# 1_Power.net
KiCad netlist of a schematic drawn in Altium Designer
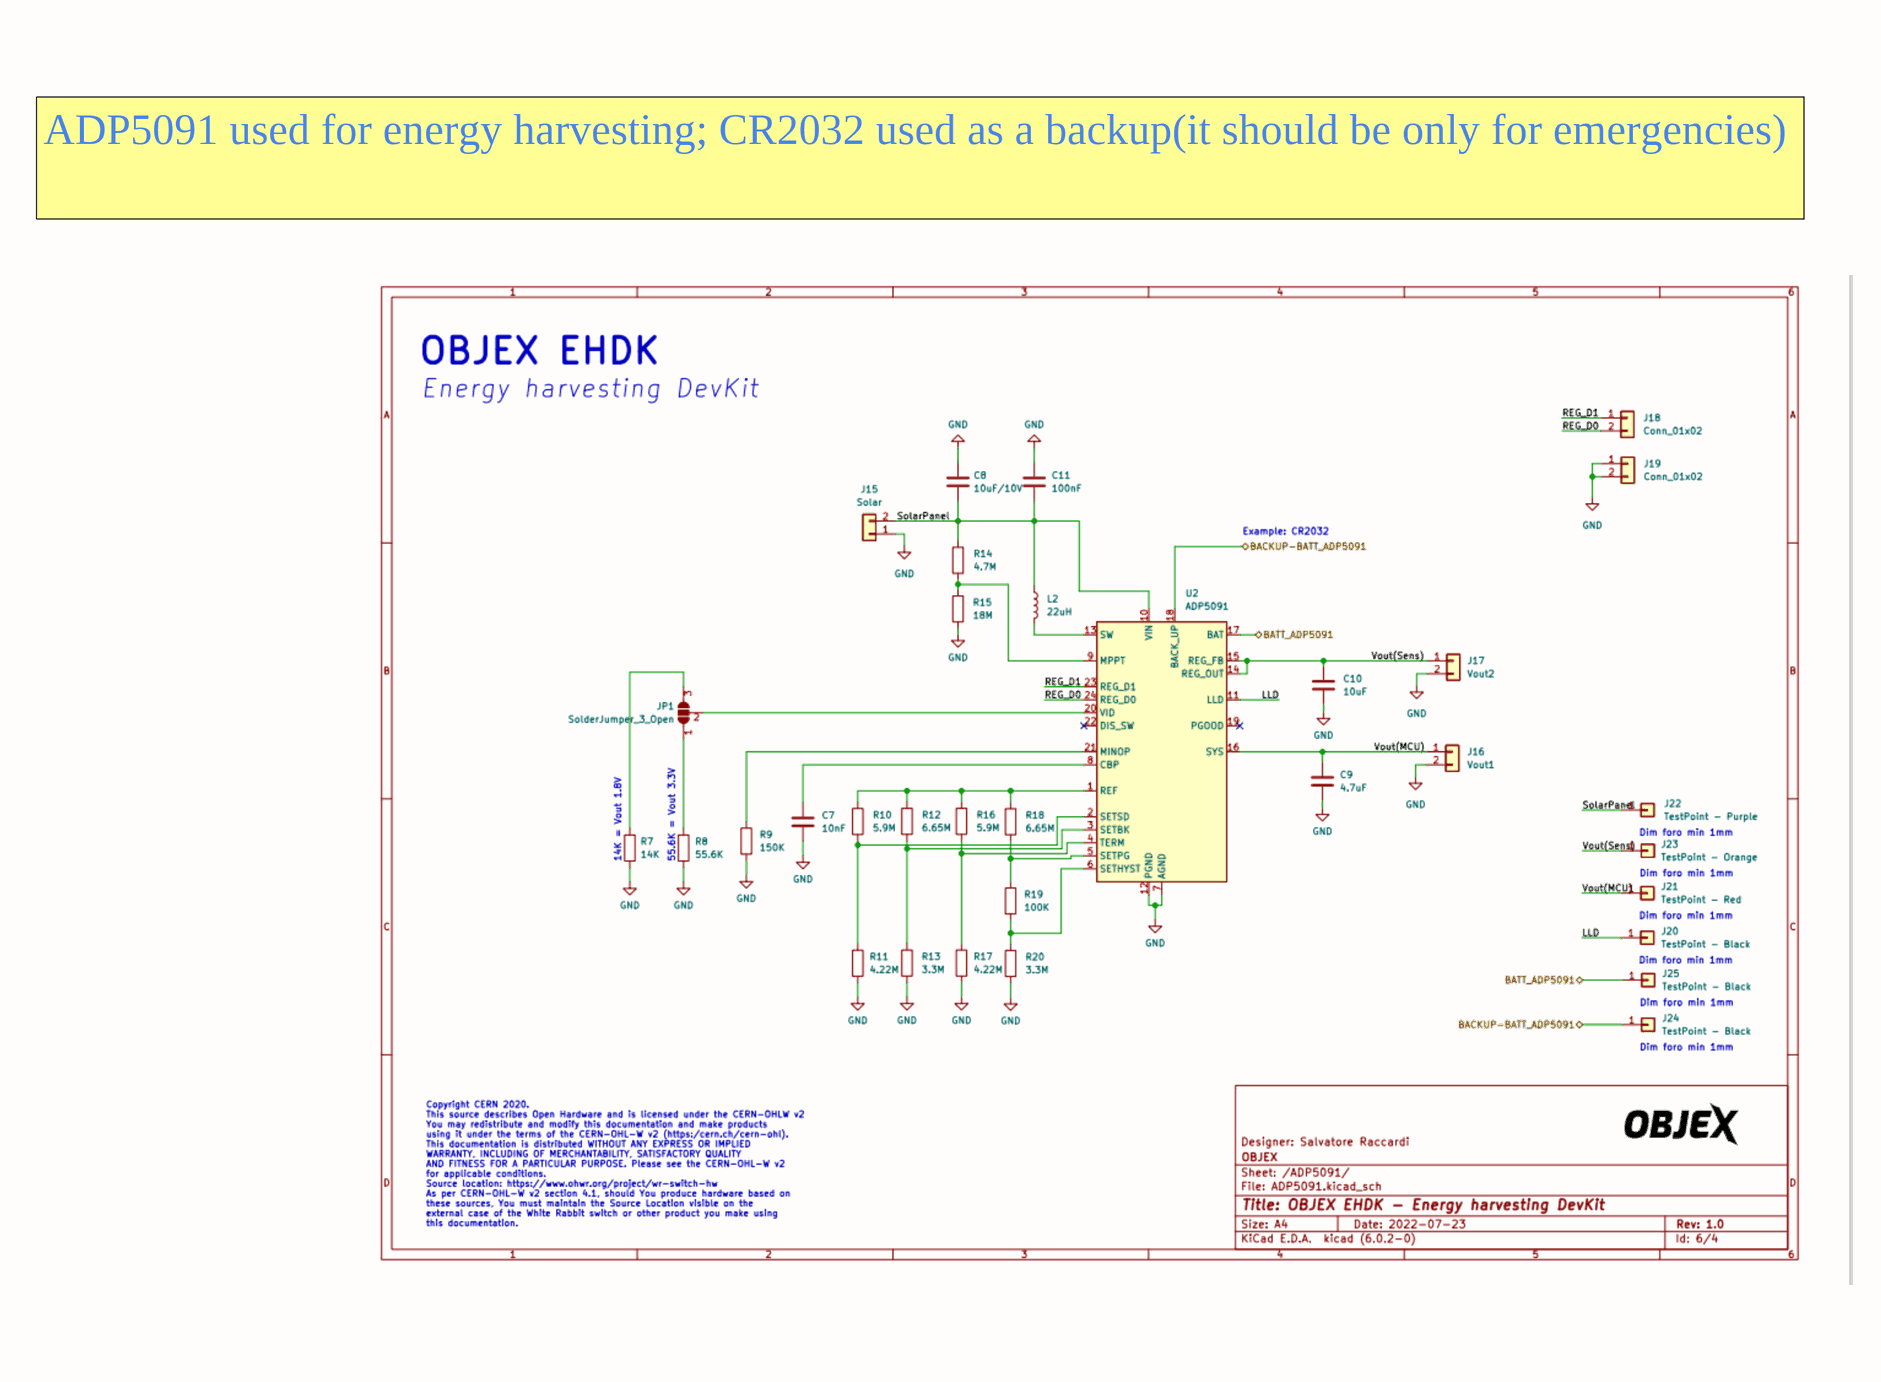
[diagram p0: 1_Power.SchDoc, left]
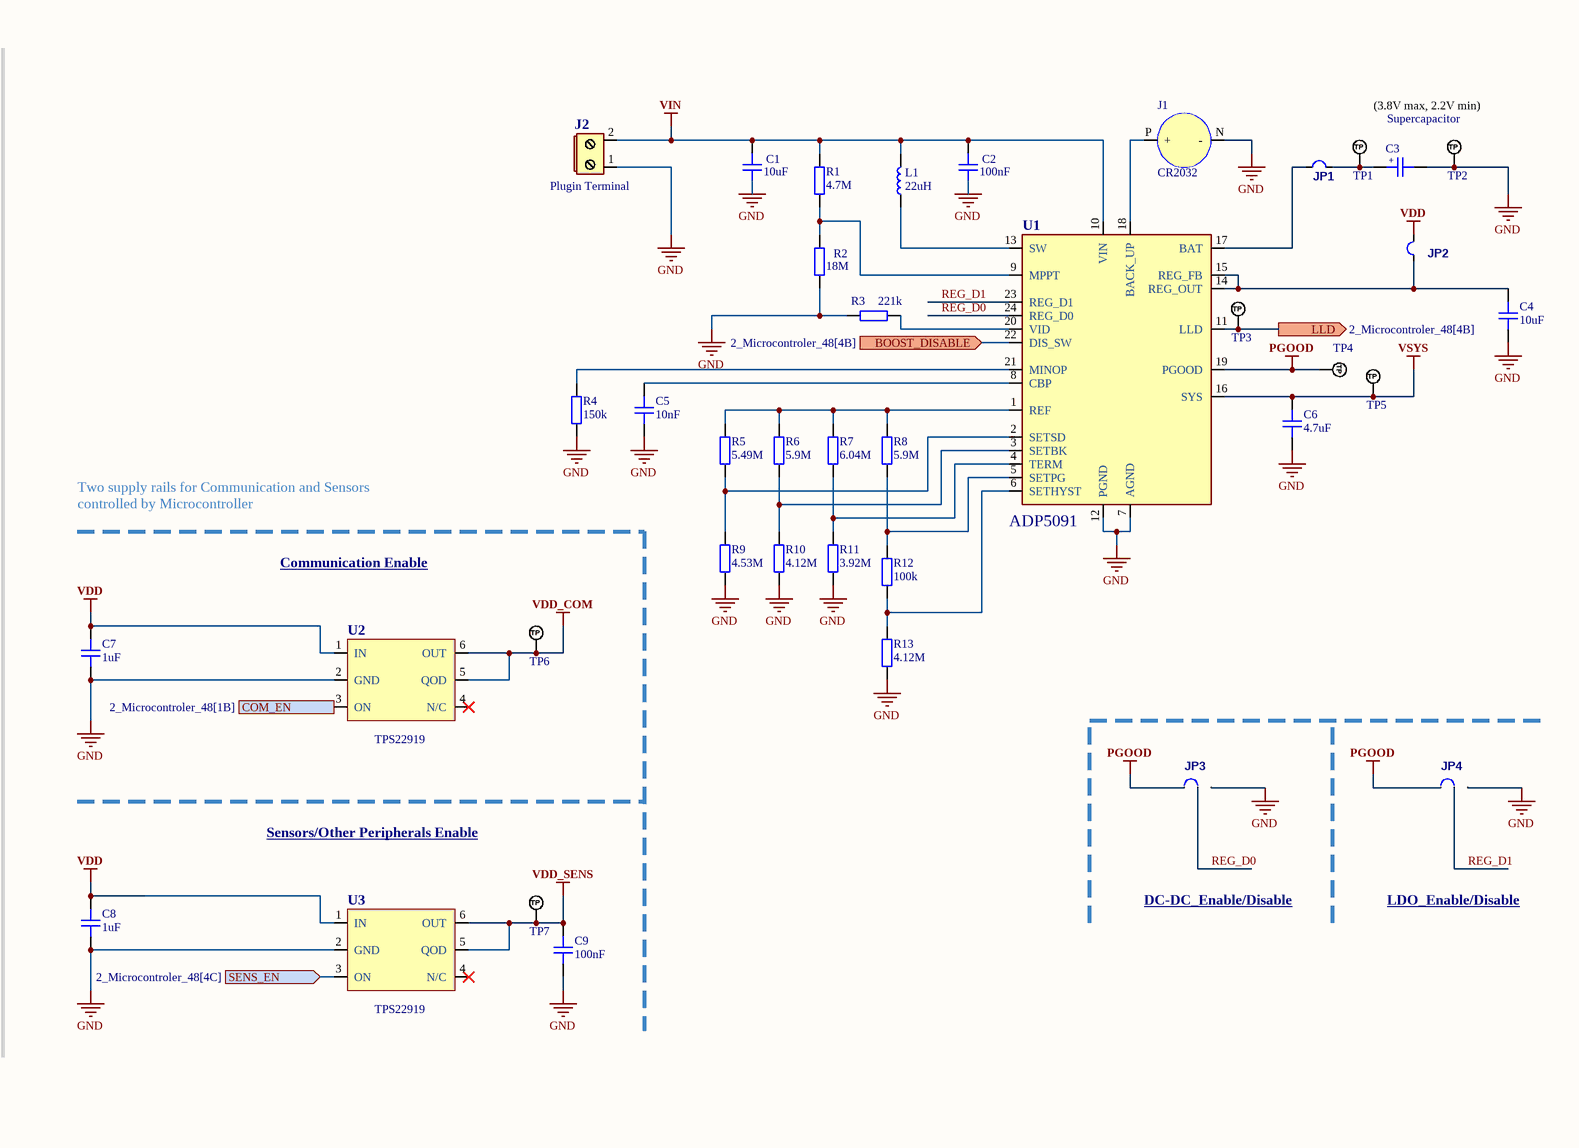
[diagram p1: 1_Power.SchDoc, middle]
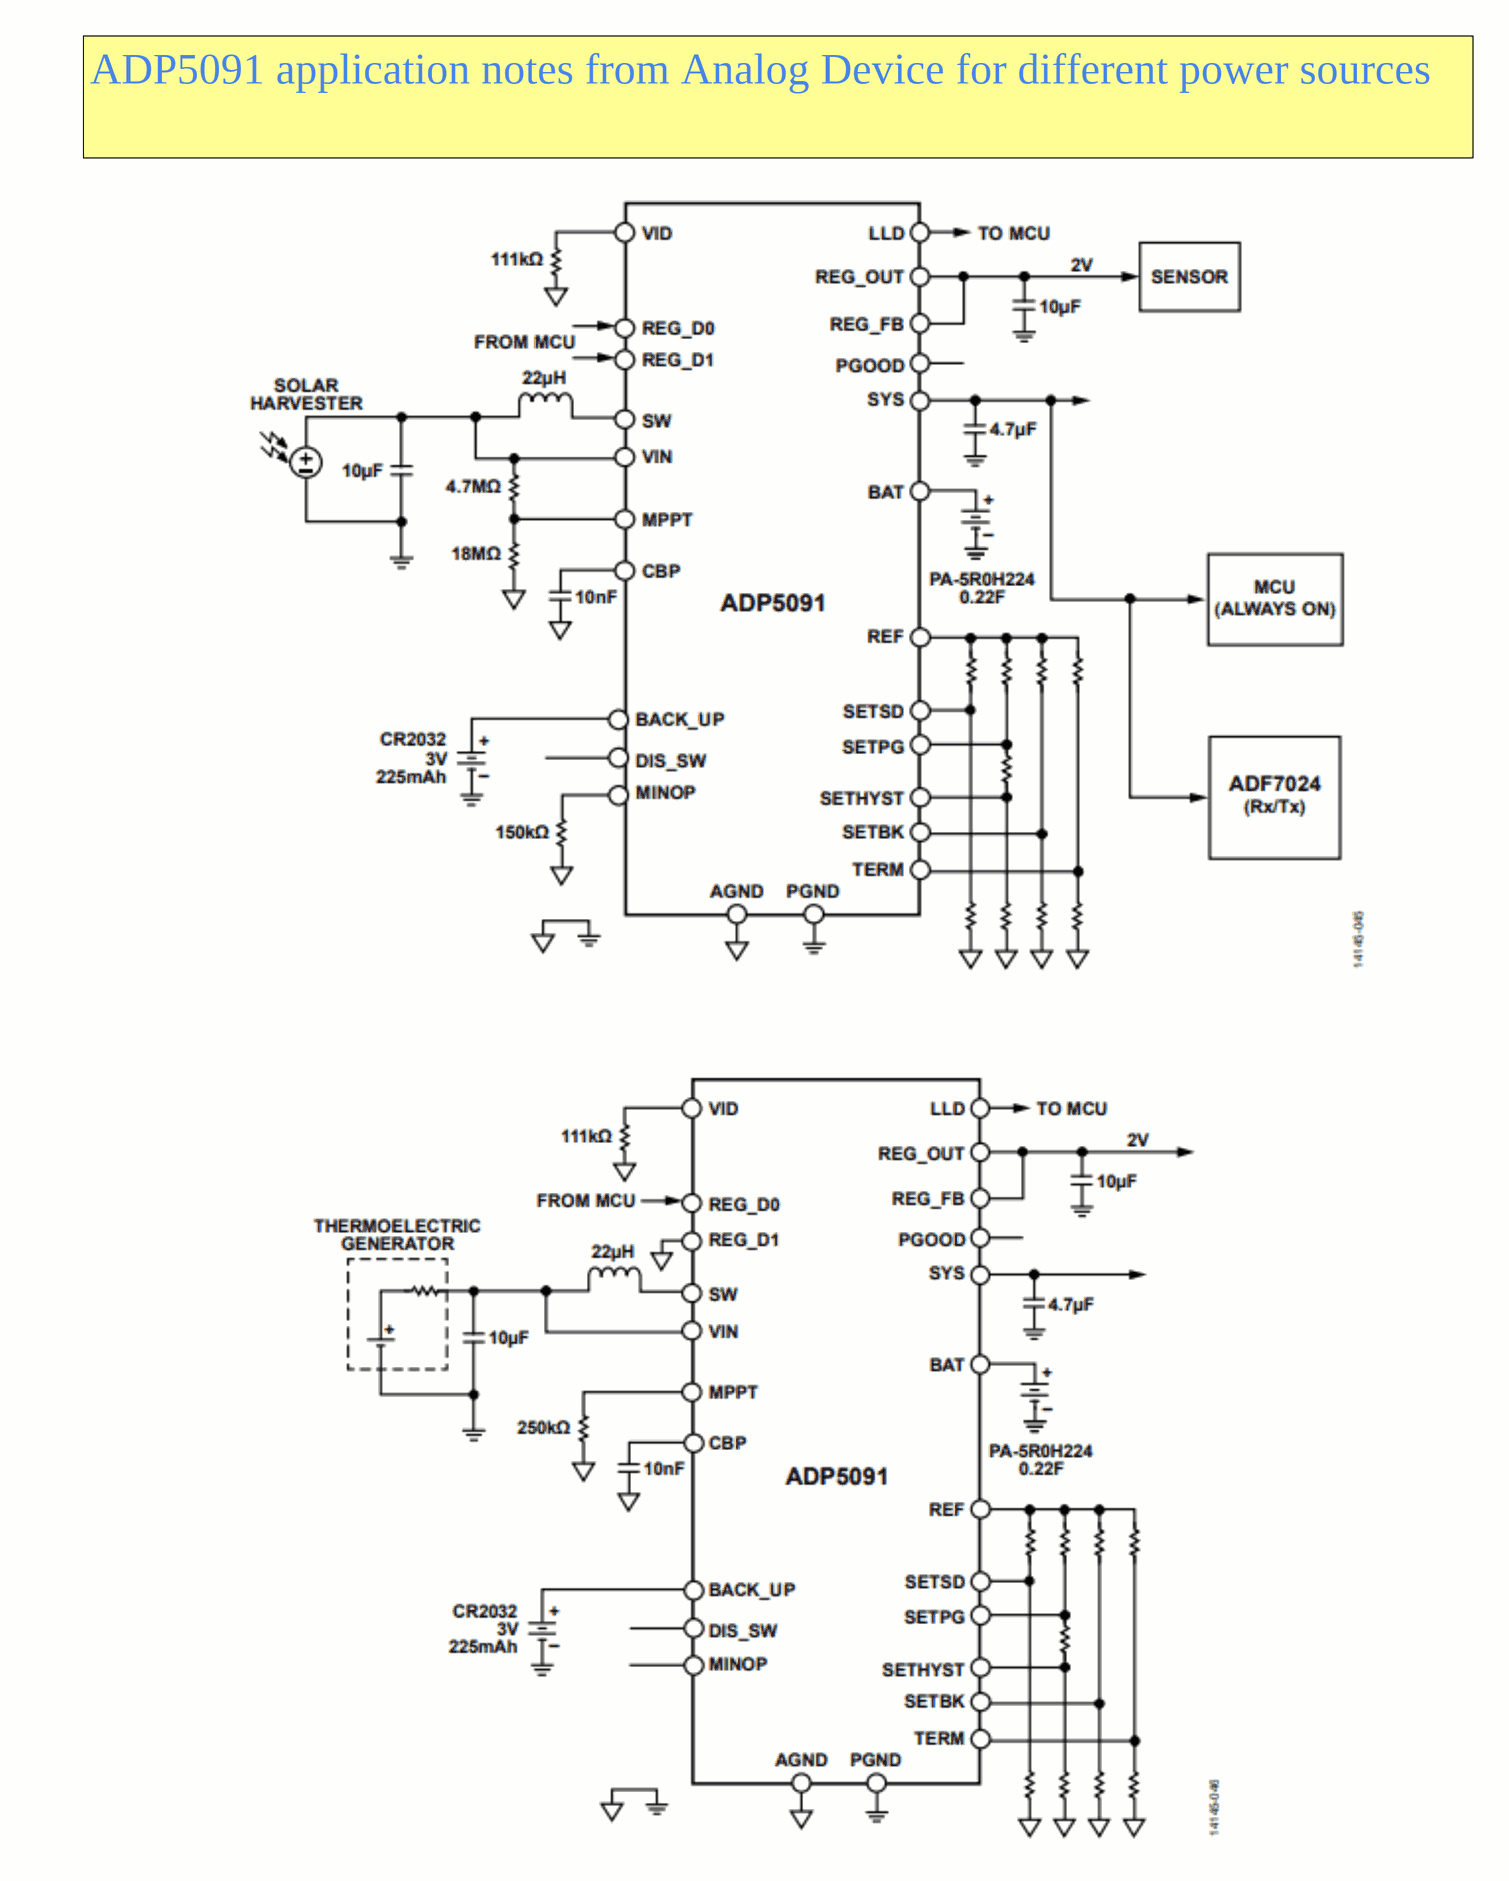
[diagram p2: 1_Power.SchDoc, right]

(export (version "E")
  (design (tool "Eeschema 10.0.6"))
  (components
    (comp (ref "C1")
      (value "10uF")
      (footprint "C0603")
      (description "Capacitor SMD 0603")
      (libsource (lib "Schlib_H2") (part "CAP_0603"))
    )
    (comp (ref "C2")
      (value "100nF")
      (footprint "C0603")
      (description "Capacitor SMD 0603")
      (libsource (lib "Schlib_H2") (part "CAP_0603"))
    )
    (comp (ref "C3")
      (value "Supercapacitor")
      (footprint "CAP_POL_8x16x3.5")
      (libsource (lib "Schlib_H2") (part "Supercapacitor"))
    )
    (comp (ref "C4")
      (value "10uF")
      (footprint "C0603")
      (description "Capacitor SMD 0603")
      (libsource (lib "Schlib_H2") (part "CAP_0603"))
    )
    (comp (ref "C5")
      (value "10nF")
      (footprint "C0603")
      (description "Capacitor SMD 0603")
      (libsource (lib "Schlib_H2") (part "CAP_0603"))
    )
    (comp (ref "C6")
      (value "4.7uF")
      (footprint "C0603")
      (description "Capacitor SMD 0603")
      (libsource (lib "Schlib_H2") (part "CAP_0603"))
    )
    (comp (ref "C7")
      (value "1uF")
      (footprint "C0603")
      (description "Capacitor SMD 0603")
      (libsource (lib "Schlib_H2") (part "CAP_0603"))
    )
    (comp (ref "C8")
      (value "1uF")
      (footprint "C0603")
      (description "Capacitor SMD 0603")
      (libsource (lib "Schlib_H2") (part "CAP_0603"))
    )
    (comp (ref "C9")
      (value "100nF")
      (footprint "C0603")
      (description "Capacitor SMD 0603")
      (libsource (lib "Schlib_H2") (part "CAP_0603"))
    )
    (comp (ref "J1")
      (value "CR2032")
      (footprint "BAT_CR2032-BS-6-1")
      (description "CR2032 Coin Cell Battery Holder")
      (fields (field (name "MANUFACTURER") "Q&J") (field (name "MANUFACTURER PART NUMBER") "CR2032-BS-6-1"))
      (libsource (lib "Schlib_H2") (part "CR2032-BS-6-1"))
    )
    (comp (ref "J2")
      (value "Plugin Terminal")
      (footprint "2.54_pluggable_terminal")
      (description "Screw terminal or plug terminal for power")
      (libsource (lib "Schlib_H2") (part "Power_Connector"))
    )
    (comp (ref "JP1")
      (value "JUMPER")
      (footprint "HEADER_1x2_2.54")
      (libsource (lib "Schlib_H2") (part "JUMPER"))
    )
    (comp (ref "JP2") (value "JUMPER") (footprint "HEADER_1x2_2.54") (libsource (lib "") (part "JUMPER_1")))
    (comp (ref "JP3")
      (value "JUMPER_3PIN")
      (footprint "HEADER_1x3_2.54")
      (libsource (lib "Schlib_H2") (part "JUMPER_3PIN"))
    )
    (comp (ref "JP4")
      (value "JUMPER_3PIN")
      (footprint "HEADER_1x3_2.54")
      (libsource (lib "Schlib_H2") (part "JUMPER_3PIN"))
    )
    (comp (ref "L1")
      (value "22uH")
      (footprint "IND_3.2_4")
      (description "Inductor SMD 1008")
      (libsource (lib "Schlib_H2") (part "IND_1008"))
    )
    (comp (ref "R1")
      (value "4.7M")
      (footprint "R0603")
      (description "Resistor SMD 0603")
      (libsource (lib "Schlib_H2") (part "RES_0603"))
    )
    (comp (ref "R2")
      (value "18M")
      (footprint "R0603")
      (description "Resistor SMD 0603")
      (libsource (lib "Schlib_H2") (part "RES_0603"))
    )
    (comp (ref "R3")
      (value "221k")
      (footprint "R0603")
      (description "Resistor SMD 0603")
      (libsource (lib "Schlib_H2") (part "RES_0603"))
    )
    (comp (ref "R4")
      (value "150k")
      (footprint "R0603")
      (description "Resistor SMD 0603")
      (libsource (lib "Schlib_H2") (part "RES_0603"))
    )
    (comp (ref "R5")
      (value "5.49M")
      (footprint "R0603")
      (description "Resistor SMD 0603")
      (libsource (lib "Schlib_H2") (part "RES_0603"))
    )
    (comp (ref "R6")
      (value "5.9M")
      (footprint "R0603")
      (description "Resistor SMD 0603")
      (libsource (lib "Schlib_H2") (part "RES_0603"))
    )
    (comp (ref "R7")
      (value "6.04M")
      (footprint "R0603")
      (description "Resistor SMD 0603")
      (libsource (lib "Schlib_H2") (part "RES_0603"))
    )
    (comp (ref "R8")
      (value "5.9M")
      (footprint "R0603")
      (description "Resistor SMD 0603")
      (libsource (lib "Schlib_H2") (part "RES_0603"))
    )
    (comp (ref "R9")
      (value "4.53M")
      (footprint "R0603")
      (description "Resistor SMD 0603")
      (libsource (lib "Schlib_H2") (part "RES_0603"))
    )
    (comp (ref "R10")
      (value "4.12M")
      (footprint "R0603")
      (description "Resistor SMD 0603")
      (libsource (lib "Schlib_H2") (part "RES_0603"))
    )
    (comp (ref "R11")
      (value "3.92M")
      (footprint "R0603")
      (description "Resistor SMD 0603")
      (libsource (lib "Schlib_H2") (part "RES_0603"))
    )
    (comp (ref "R12")
      (value "100k")
      (footprint "R0603")
      (description "Resistor SMD 0603")
      (libsource (lib "Schlib_H2") (part "RES_0603"))
    )
    (comp (ref "R13")
      (value "4.12M")
      (footprint "R0603")
      (description "Resistor SMD 0603")
      (libsource (lib "Schlib_H2") (part "RES_0603"))
    )
    (comp (ref "TP1")
      (value "TP_NOBOM")
      (footprint "TEST_PAD_THD")
      (description "Test Point Round 1mm (NO BOM)")
      (libsource (lib "Schlib_H2") (part "TEST_POINT_RND_1MM"))
    )
    (comp (ref "TP2")
      (value "TP_NOBOM")
      (footprint "TEST_PAD_THD")
      (description "Test Point Round 1mm (NO BOM)")
      (libsource (lib "Schlib_H2") (part "TEST_POINT_RND_1MM"))
    )
    (comp (ref "TP3")
      (value "TP_NOBOM")
      (footprint "TEST_PAD_THD")
      (description "Test Point Round 1mm (NO BOM)")
      (libsource (lib "Schlib_H2") (part "TEST_POINT_RND_1MM"))
    )
    (comp (ref "TP4")
      (value "TP_NOBOM")
      (footprint "TEST_PAD_THD")
      (description "Test Point Round 1mm (NO BOM)")
      (libsource (lib "Schlib_H2") (part "TEST_POINT_RND_1MM"))
    )
    (comp (ref "TP5")
      (value "TP_NOBOM")
      (footprint "TEST_PAD_THD")
      (description "Test Point Round 1mm (NO BOM)")
      (libsource (lib "Schlib_H2") (part "TEST_POINT_RND_1MM"))
    )
    (comp (ref "TP6")
      (value "TP_NOBOM")
      (footprint "TEST_PAD_THD")
      (description "Test Point Round 1mm (NO BOM)")
      (libsource (lib "Schlib_H2") (part "TEST_POINT_RND_1MM"))
    )
    (comp (ref "TP7")
      (value "TP_NOBOM")
      (footprint "TEST_PAD_THD")
      (description "Test Point Round 1mm (NO BOM)")
      (libsource (lib "Schlib_H2") (part "TEST_POINT_RND_1MM"))
    )
    (comp (ref "U1")
      (value "ADP5091")
      (footprint "LFCSP-24")
      (description "Ultralow Power Energy Harvester PMUs \r\nwith MPPT and Charge Management and BAckup Supply")
      (libsource (lib "Schlib_H2") (part "ADP5091"))
    )
    (comp (ref "U2")
      (value "TPS22919")
      (footprint "SC70-6")
      (description "5.5-V, 1.5-A, 90-mΩ load switch with adjustable output discharge")
      (libsource (lib "Schlib_H2") (part "TPS22919"))
    )
    (comp (ref "U3")
      (value "TPS22919")
      (footprint "SC70-6")
      (description "5.5-V, 1.5-A, 90-mΩ load switch with adjustable output discharge")
      (libsource (lib "Schlib_H2") (part "TPS22919"))
    )
  )
  (nets
    (net (code "1") (name "/BOOST_DISABLE") (class "Default")
      (node (ref "U1") (pin "22") (pinfunction "DIS_SW_22") (pintype "passive"))
    )
    (net (code "2") (name "/COM_EN") (class "Default")
      (node (ref "U2") (pin "3") (pinfunction "ON_3") (pintype "passive"))
    )
    (net (code "3") (name "/LLD") (class "Default")
      (node (ref "TP3") (pin "1") (pinfunction "TP_1") (pintype "passive"))
      (node (ref "U1") (pin "11") (pinfunction "LLD_11") (pintype "passive"))
    )
    (net (code "4") (name "/REG_D0") (class "Default")
      (node (ref "JP3") (pin "2") (pinfunction "2_2") (pintype "passive"))
      (node (ref "U1") (pin "24") (pinfunction "REG_D0_24") (pintype "passive"))
    )
    (net (code "5") (name "/REG_D1") (class "Default")
      (node (ref "JP4") (pin "2") (pinfunction "2_2") (pintype "passive"))
      (node (ref "U1") (pin "23") (pinfunction "REG_D1_23") (pintype "passive"))
    )
    (net (code "6") (name "/SENS_EN") (class "Default")
      (node (ref "U3") (pin "3") (pinfunction "ON_3") (pintype "passive"))
    )
    (net (code "7") (name "GND") (class "Default")
      (node (ref "C1") (pin "1") (pinfunction "1_1") (pintype "passive"))
      (node (ref "C2") (pin "1") (pinfunction "1_1") (pintype "passive"))
      (node (ref "C3") (pin "2") (pinfunction "2_2") (pintype "passive"))
      (node (ref "C4") (pin "1") (pinfunction "1_1") (pintype "passive"))
      (node (ref "C5") (pin "1") (pinfunction "1_1") (pintype "passive"))
      (node (ref "C6") (pin "1") (pinfunction "1_1") (pintype "passive"))
      (node (ref "C7") (pin "1") (pinfunction "1_1") (pintype "passive"))
      (node (ref "C8") (pin "1") (pinfunction "1_1") (pintype "passive"))
      (node (ref "C9") (pin "1") (pinfunction "1_1") (pintype "passive"))
      (node (ref "J1") (pin "N") (pinfunction "-_N") (pintype "passive"))
      (node (ref "J2") (pin "1") (pinfunction "1_1") (pintype "passive"))
      (node (ref "JP3") (pin "3") (pinfunction "3_3") (pintype "passive"))
      (node (ref "JP4") (pin "3") (pinfunction "3_3") (pintype "passive"))
      (node (ref "R10") (pin "1") (pinfunction "1_1") (pintype "passive"))
      (node (ref "R11") (pin "1") (pinfunction "1_1") (pintype "passive"))
      (node (ref "R13") (pin "1") (pinfunction "1_1") (pintype "passive"))
      (node (ref "R2") (pin "1") (pinfunction "1_1") (pintype "passive"))
      (node (ref "R3") (pin "1") (pinfunction "1_1") (pintype "passive"))
      (node (ref "R4") (pin "1") (pinfunction "1_1") (pintype "passive"))
      (node (ref "R9") (pin "1") (pinfunction "1_1") (pintype "passive"))
      (node (ref "TP2") (pin "1") (pinfunction "TP_1") (pintype "passive"))
      (node (ref "U1") (pin "12") (pinfunction "PGND_12") (pintype "passive"))
      (node (ref "U1") (pin "7") (pinfunction "AGND_7") (pintype "passive"))
      (node (ref "U2") (pin "2") (pinfunction "GND_2") (pintype "passive"))
      (node (ref "U3") (pin "2") (pinfunction "GND_2") (pintype "passive"))
    )
    (net (code "8") (name "Net-(J1-+)") (class "Default")
      (node (ref "J1") (pin "P") (pinfunction "+_P") (pintype "passive"))
      (node (ref "U1") (pin "18") (pinfunction "BACK_UP_18") (pintype "passive"))
    )
    (net (code "9") (name "Net-(TP1-TP)") (class "Default")
      (node (ref "C3") (pin "1") (pinfunction "1_1") (pintype "passive"))
      (node (ref "JP1") (pin "2") (pinfunction "2_2") (pintype "passive"))
      (node (ref "TP1") (pin "1") (pinfunction "TP_1") (pintype "passive"))
    )
    (net (code "10") (name "Net-(U1-BAT)") (class "Default")
      (node (ref "JP1") (pin "1") (pinfunction "1_1") (pintype "passive"))
      (node (ref "U1") (pin "17") (pinfunction "BAT_17") (pintype "passive"))
    )
    (net (code "11") (name "Net-(U1-CBP)") (class "Default")
      (node (ref "C5") (pin "2") (pinfunction "2_2") (pintype "passive"))
      (node (ref "U1") (pin "8") (pinfunction "CBP_8") (pintype "passive"))
    )
    (net (code "12") (name "Net-(U1-MINOP)") (class "Default")
      (node (ref "R4") (pin "2") (pinfunction "2_2") (pintype "passive"))
      (node (ref "U1") (pin "21") (pinfunction "MINOP_21") (pintype "passive"))
    )
    (net (code "13") (name "Net-(U1-MPPT)") (class "Default")
      (node (ref "R1") (pin "1") (pinfunction "1_1") (pintype "passive"))
      (node (ref "R2") (pin "2") (pinfunction "2_2") (pintype "passive"))
      (node (ref "U1") (pin "9") (pinfunction "MPPT_9") (pintype "passive"))
    )
    (net (code "14") (name "Net-(U1-REF)") (class "Default")
      (node (ref "R5") (pin "2") (pinfunction "2_2") (pintype "passive"))
      (node (ref "R6") (pin "2") (pinfunction "2_2") (pintype "passive"))
      (node (ref "R7") (pin "2") (pinfunction "2_2") (pintype "passive"))
      (node (ref "R8") (pin "2") (pinfunction "2_2") (pintype "passive"))
      (node (ref "U1") (pin "1") (pinfunction "REF_1") (pintype "passive"))
    )
    (net (code "15") (name "Net-(U1-REG_FB)") (class "Default")
      (node (ref "C4") (pin "2") (pinfunction "2_2") (pintype "passive"))
      (node (ref "JP2") (pin "1") (pinfunction "1_1") (pintype "passive"))
      (node (ref "U1") (pin "14") (pinfunction "REG_OUT_14") (pintype "passive"))
      (node (ref "U1") (pin "15") (pinfunction "REG_FB_15") (pintype "passive"))
    )
    (net (code "16") (name "Net-(U1-SETBK)") (class "Default")
      (node (ref "R10") (pin "2") (pinfunction "2_2") (pintype "passive"))
      (node (ref "R6") (pin "1") (pinfunction "1_1") (pintype "passive"))
      (node (ref "U1") (pin "3") (pinfunction "SETBK_3") (pintype "passive"))
    )
    (net (code "17") (name "Net-(U1-SETHYST)") (class "Default")
      (node (ref "R12") (pin "1") (pinfunction "1_1") (pintype "passive"))
      (node (ref "R13") (pin "2") (pinfunction "2_2") (pintype "passive"))
      (node (ref "U1") (pin "6") (pinfunction "SETHYST_6") (pintype "passive"))
    )
    (net (code "18") (name "Net-(U1-SETPG)") (class "Default")
      (node (ref "R12") (pin "2") (pinfunction "2_2") (pintype "passive"))
      (node (ref "R8") (pin "1") (pinfunction "1_1") (pintype "passive"))
      (node (ref "U1") (pin "5") (pinfunction "SETPG_5") (pintype "passive"))
    )
    (net (code "19") (name "Net-(U1-SETSD)") (class "Default")
      (node (ref "R5") (pin "1") (pinfunction "1_1") (pintype "passive"))
      (node (ref "R9") (pin "2") (pinfunction "2_2") (pintype "passive"))
      (node (ref "U1") (pin "2") (pinfunction "SETSD_2") (pintype "passive"))
    )
    (net (code "20") (name "Net-(U1-SW)") (class "Default")
      (node (ref "L1") (pin "1") (pinfunction "1_1") (pintype "passive"))
      (node (ref "U1") (pin "13") (pinfunction "SW_13") (pintype "passive"))
    )
    (net (code "21") (name "Net-(U1-TERM)") (class "Default")
      (node (ref "R11") (pin "2") (pinfunction "2_2") (pintype "passive"))
      (node (ref "R7") (pin "1") (pinfunction "1_1") (pintype "passive"))
      (node (ref "U1") (pin "4") (pinfunction "TERM_4") (pintype "passive"))
    )
    (net (code "22") (name "Net-(U1-VID)") (class "Default")
      (node (ref "R3") (pin "2") (pinfunction "2_2") (pintype "passive"))
      (node (ref "U1") (pin "20") (pinfunction "VID_20") (pintype "passive"))
    )
    (net (code "23") (name "PGOOD") (class "Default")
      (node (ref "JP3") (pin "1") (pinfunction "1_1") (pintype "passive"))
      (node (ref "JP4") (pin "1") (pinfunction "1_1") (pintype "passive"))
      (node (ref "TP4") (pin "1") (pinfunction "TP_1") (pintype "passive"))
      (node (ref "U1") (pin "19") (pinfunction "PGOOD_19") (pintype "passive"))
    )
    (net (code "24") (name "VDD") (class "Default")
      (node (ref "C7") (pin "2") (pinfunction "2_2") (pintype "passive"))
      (node (ref "C8") (pin "2") (pinfunction "2_2") (pintype "passive"))
      (node (ref "JP2") (pin "2") (pinfunction "2_2") (pintype "passive"))
      (node (ref "U2") (pin "1") (pinfunction "IN_1") (pintype "passive"))
      (node (ref "U3") (pin "1") (pinfunction "IN_1") (pintype "passive"))
    )
    (net (code "25") (name "VDD_COM") (class "Default")
      (node (ref "TP6") (pin "1") (pinfunction "TP_1") (pintype "passive"))
      (node (ref "U2") (pin "5") (pinfunction "QOD_5") (pintype "passive"))
      (node (ref "U2") (pin "6") (pinfunction "OUT_6") (pintype "passive"))
    )
    (net (code "26") (name "VDD_SENS") (class "Default")
      (node (ref "C9") (pin "2") (pinfunction "2_2") (pintype "passive"))
      (node (ref "TP7") (pin "1") (pinfunction "TP_1") (pintype "passive"))
      (node (ref "U3") (pin "5") (pinfunction "QOD_5") (pintype "passive"))
      (node (ref "U3") (pin "6") (pinfunction "OUT_6") (pintype "passive"))
    )
    (net (code "27") (name "VIN") (class "Default")
      (node (ref "C1") (pin "2") (pinfunction "2_2") (pintype "passive"))
      (node (ref "C2") (pin "2") (pinfunction "2_2") (pintype "passive"))
      (node (ref "J2") (pin "2") (pinfunction "2_2") (pintype "passive"))
      (node (ref "L1") (pin "2") (pinfunction "2_2") (pintype "passive"))
      (node (ref "R1") (pin "2") (pinfunction "2_2") (pintype "passive"))
      (node (ref "U1") (pin "10") (pinfunction "VIN_10") (pintype "passive"))
    )
    (net (code "28") (name "VSYS") (class "Default")
      (node (ref "C6") (pin "2") (pinfunction "2_2") (pintype "passive"))
      (node (ref "TP5") (pin "1") (pinfunction "TP_1") (pintype "passive"))
      (node (ref "U1") (pin "16") (pinfunction "SYS_16") (pintype "passive"))
    )
    (net (code "29") (name "unconnected-(U2-N{slash}C-Pad4)") (class "Default")
      (node (ref "U2") (pin "4") (pinfunction "N/C_4") (pintype "passive+no_connect"))
    )
    (net (code "30") (name "unconnected-(U3-N{slash}C-Pad4)") (class "Default")
      (node (ref "U3") (pin "4") (pinfunction "N/C_4") (pintype "passive+no_connect"))
    )
  )
)
